# MAGBOT21.net
KiCad netlist of a schematic drawn in EAGLE
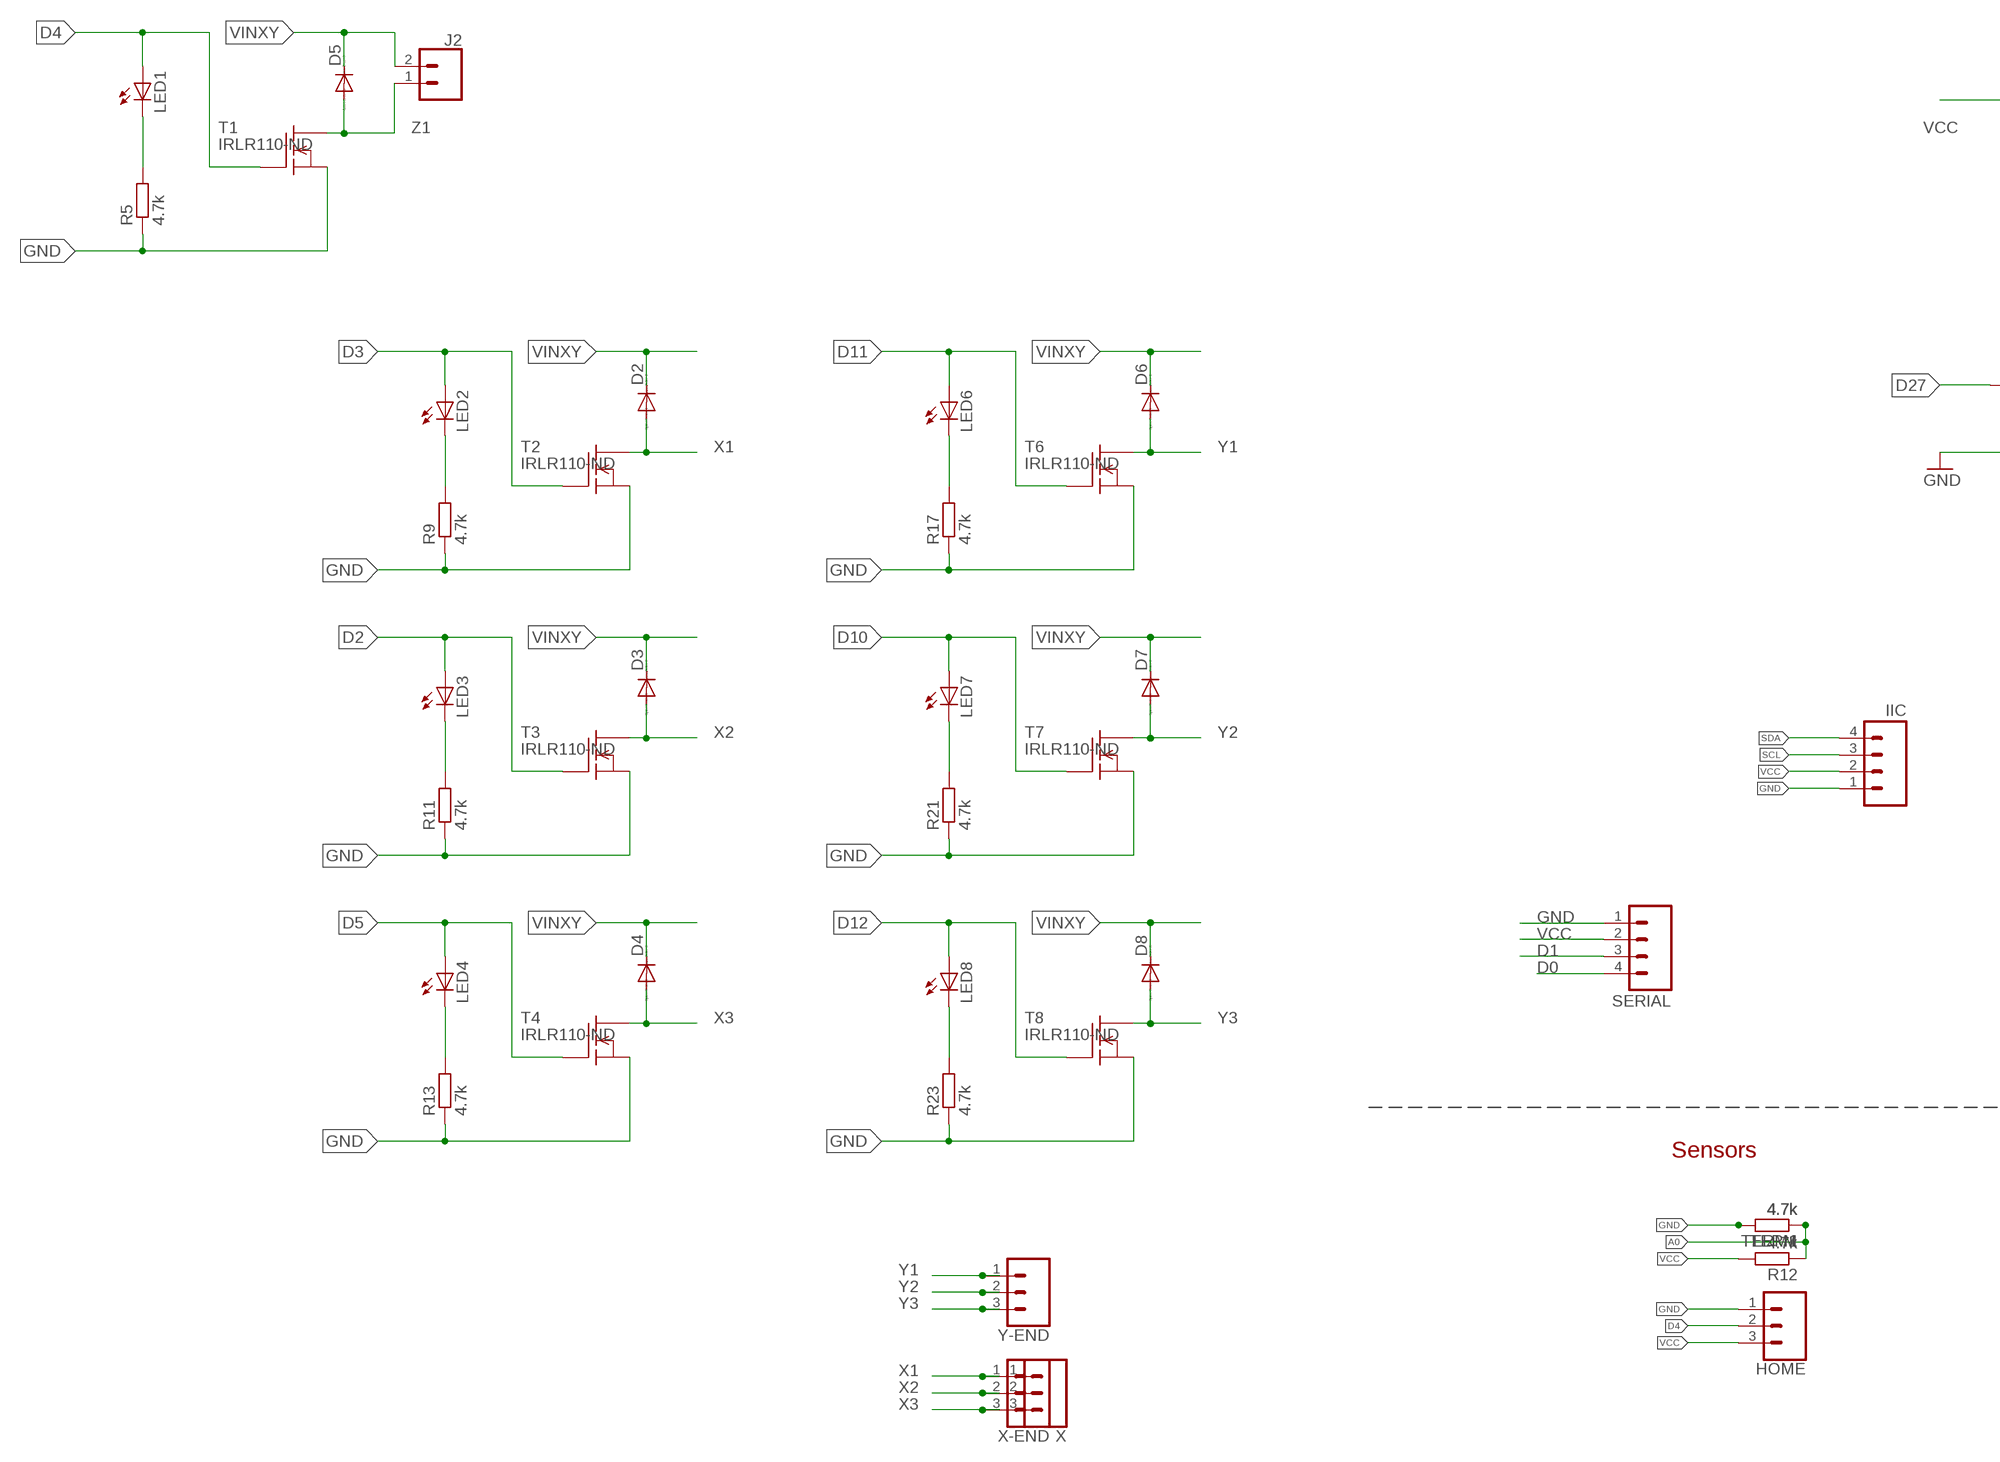
[diagram p0: schematic, sheet 1, part 1 of 2]
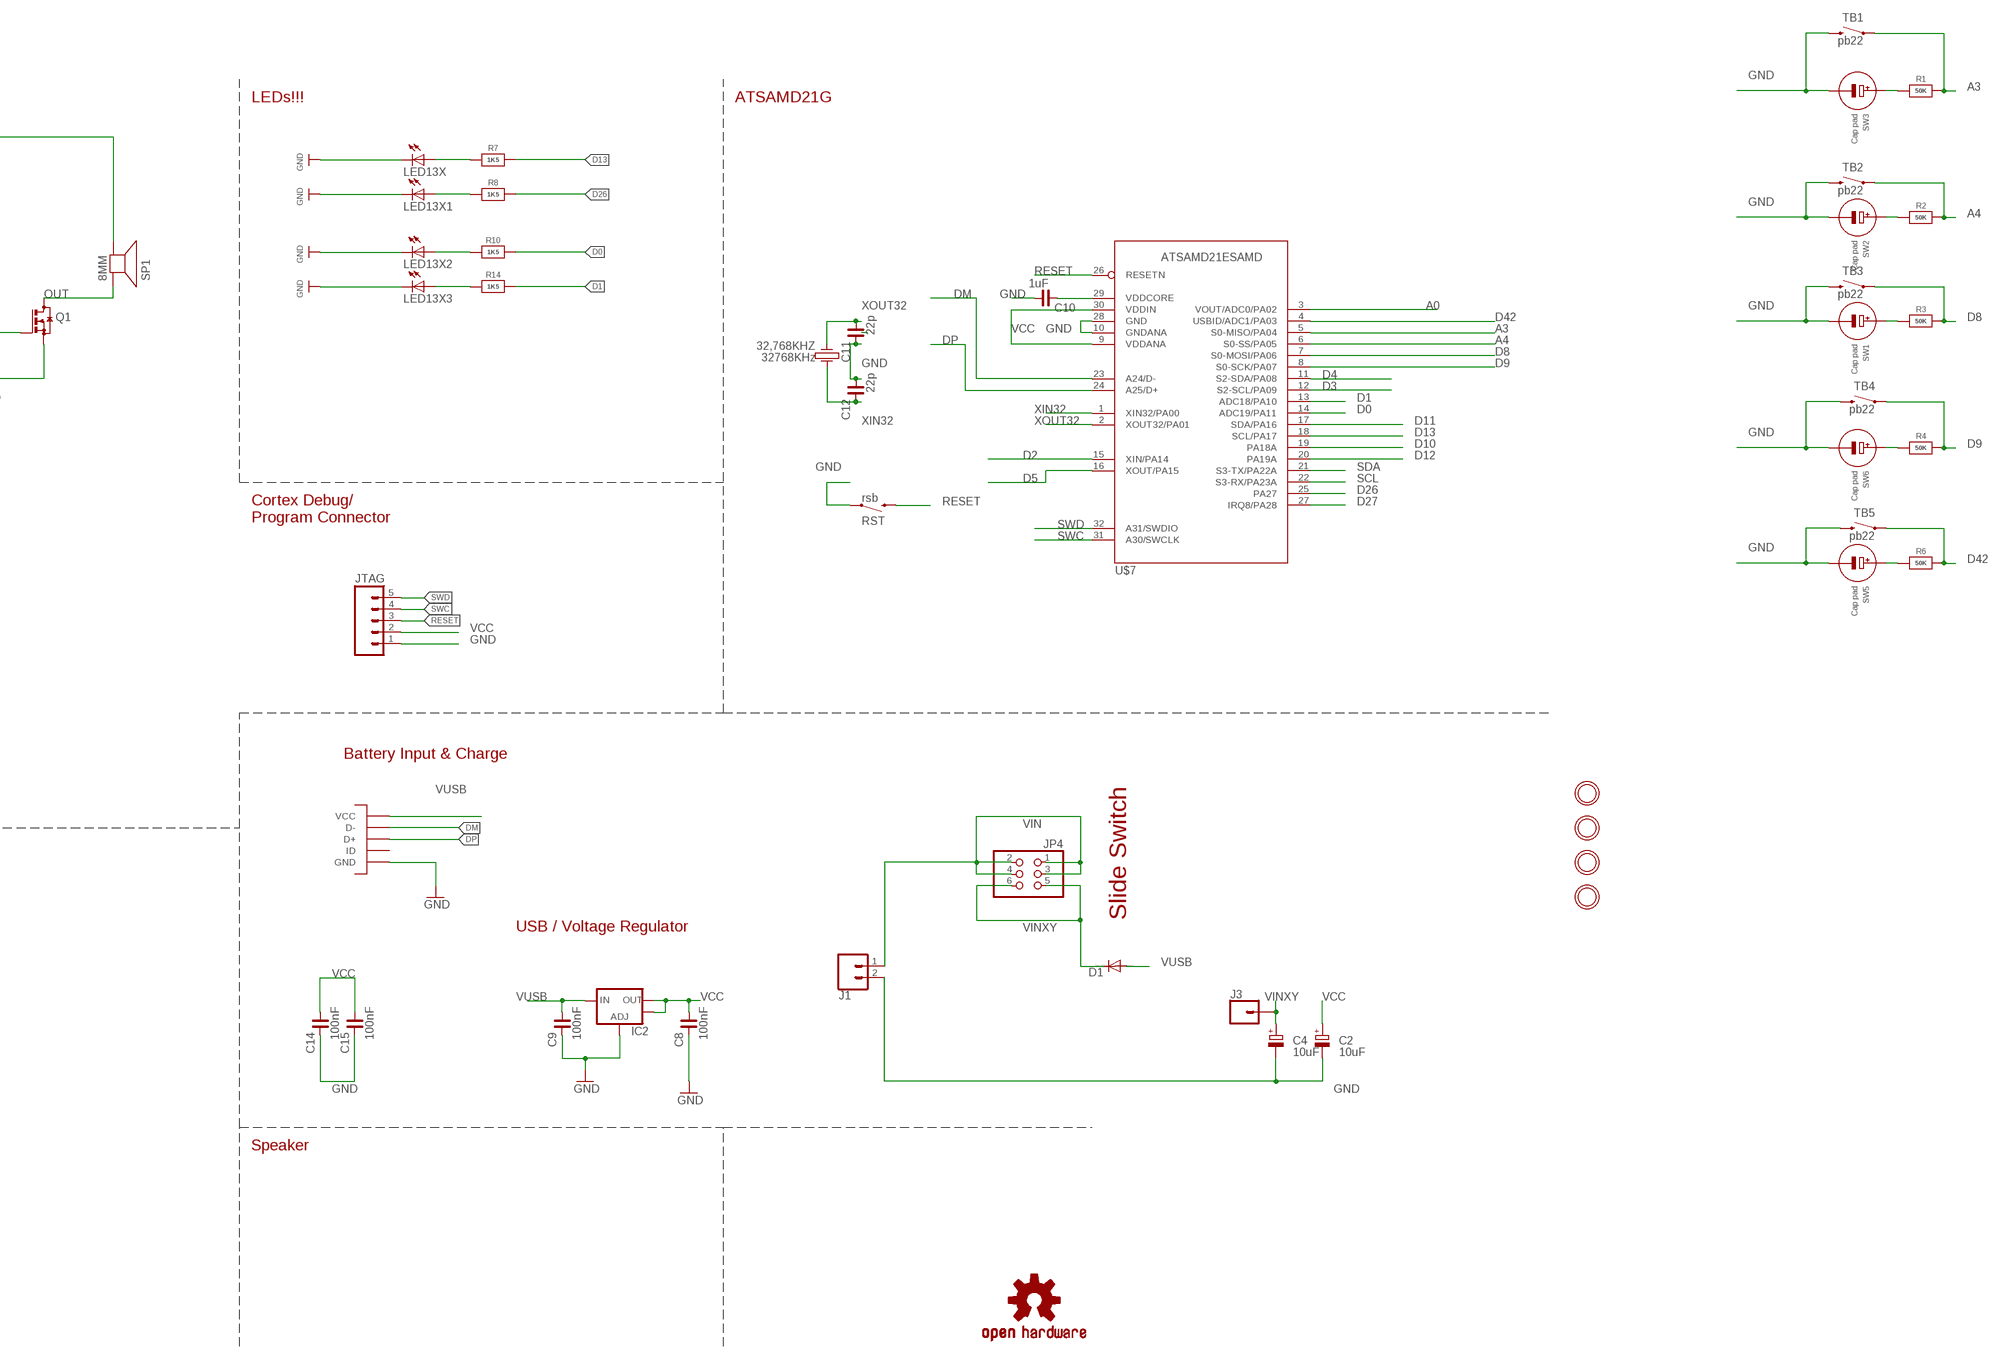
[diagram p1: schematic, sheet 1, part 2 of 2]

(export (version "E")
  (design (tool "Eeschema 10.0.6"))
  (components
    (comp (ref "32,768KHZ")
      (value "32768KHz")
      (footprint "eagle-import:KX-327LT")
      (libsource (lib "eagle-import") (part "CRYSTALL"))
    )
    (comp (ref "C2")
      (value "10uF")
      (footprint "eagle-import:153CLV-0605")
      (libsource (lib "eagle-import") (part "CPOL-EU153CLV-0605"))
    )
    (comp (ref "C4")
      (value "10uF")
      (footprint "eagle-import:153CLV-0605")
      (libsource (lib "eagle-import") (part "CPOL-EU153CLV-0605"))
    )
    (comp (ref "C8")
      (value "100nF")
      (footprint "eagle-import:C0603")
      (libsource (lib "eagle-import") (part "C_0603"))
    )
    (comp (ref "C9")
      (value "100nF")
      (footprint "eagle-import:C0603")
      (libsource (lib "eagle-import") (part "C_0603"))
    )
    (comp (ref "C10")
      (value "1uF")
      (footprint "eagle-import:C0805")
      (libsource (lib "eagle-import") (part "C_0805"))
    )
    (comp (ref "C11")
      (value "22p")
      (footprint "eagle-import:C0805")
      (libsource (lib "eagle-import") (part "C_0805"))
    )
    (comp (ref "C12")
      (value "22p")
      (footprint "eagle-import:C0805")
      (libsource (lib "eagle-import") (part "C_0805"))
    )
    (comp (ref "C14")
      (value "100nF")
      (footprint "eagle-import:C0805")
      (libsource (lib "eagle-import") (part "C_0805"))
    )
    (comp (ref "C15")
      (value "100nF")
      (footprint "eagle-import:C0805")
      (libsource (lib "eagle-import") (part "C_0805"))
    )
    (comp (ref "D1")
      (value "DIODE-DO214AC")
      (footprint "eagle-import:DO214AC")
      (libsource (lib "eagle-import") (part "DIODE-DO214AC"))
    )
    (comp (ref "D2")
      (value "DIODE-DO214AC")
      (footprint "eagle-import:DO214AC")
      (libsource (lib "eagle-import") (part "DIODE-DO214AC"))
    )
    (comp (ref "D3")
      (value "DIODE-DO214AC")
      (footprint "eagle-import:DO214AC")
      (libsource (lib "eagle-import") (part "DIODE-DO214AC"))
    )
    (comp (ref "D4")
      (value "DIODE-DO214AC")
      (footprint "eagle-import:DO214AC")
      (libsource (lib "eagle-import") (part "DIODE-DO214AC"))
    )
    (comp (ref "D5")
      (value "DIODE-DO214AC")
      (footprint "eagle-import:DO214AC")
      (libsource (lib "eagle-import") (part "DIODE-DO214AC"))
    )
    (comp (ref "D6")
      (value "DIODE-DO214AC")
      (footprint "eagle-import:DO214AC")
      (libsource (lib "eagle-import") (part "DIODE-DO214AC"))
    )
    (comp (ref "D7")
      (value "DIODE-DO214AC")
      (footprint "eagle-import:DO214AC")
      (libsource (lib "eagle-import") (part "DIODE-DO214AC"))
    )
    (comp (ref "D8")
      (value "DIODE-DO214AC")
      (footprint "eagle-import:DO214AC")
      (libsource (lib "eagle-import") (part "DIODE-DO214AC"))
    )
    (comp (ref "HOME")
      (value "CONN_031X03_NO_SILK")
      (footprint "eagle-import:1X03_NO_SILK")
      (libsource (lib "eagle-import") (part "CONN_031X03_NO_SILK"))
    )
    (comp (ref "IC2")
      (value "V_REG_LM1117SOT223")
      (footprint "eagle-import:SOT223")
      (libsource (lib "eagle-import") (part "V_REG_LM1117SOT223"))
    )
    (comp (ref "IIC")
      (value "M041X04_NO_SILK")
      (footprint "eagle-import:1X04_NO_SILK")
      (libsource (lib "eagle-import") (part "M041X04_NO_SILK"))
    )
    (comp (ref "J1")
      (value "CONN_02PTH3")
      (footprint "eagle-import:1X02_LONGPADS")
      (libsource (lib "eagle-import") (part "CONN_02PTH3"))
    )
    (comp (ref "J2")
      (value "CONN_02PTH3")
      (footprint "eagle-import:1X02_LONGPADS")
      (libsource (lib "eagle-import") (part "CONN_02PTH3"))
    )
    (comp (ref "J3")
      (value "CONN_01PTH_NO_SILK_KIT")
      (footprint "eagle-import:1X01NS_KIT")
      (libsource (lib "eagle-import") (part "CONN_01PTH_NO_SILK_KIT"))
    )
    (comp (ref "JP4")
      (value "PINHD-2X3")
      (footprint "eagle-import:2X03")
      (libsource (lib "eagle-import") (part "PINHD-2X3"))
    )
    (comp (ref "JTAG")
      (value "M051.27MM")
      (footprint "eagle-import:1X05-1.27MM")
      (libsource (lib "eagle-import") (part "M051.27MM"))
    )
    (comp (ref "LED1")
      (value "LEDCHIPLED_0805")
      (footprint "eagle-import:CHIPLED_0805")
      (libsource (lib "eagle-import") (part "LEDCHIPLED_0805"))
    )
    (comp (ref "LED2")
      (value "LEDCHIPLED_0805")
      (footprint "eagle-import:CHIPLED_0805")
      (libsource (lib "eagle-import") (part "LEDCHIPLED_0805"))
    )
    (comp (ref "LED3")
      (value "LEDCHIPLED_0805")
      (footprint "eagle-import:CHIPLED_0805")
      (libsource (lib "eagle-import") (part "LEDCHIPLED_0805"))
    )
    (comp (ref "LED4")
      (value "LEDCHIPLED_0805")
      (footprint "eagle-import:CHIPLED_0805")
      (libsource (lib "eagle-import") (part "LEDCHIPLED_0805"))
    )
    (comp (ref "LED6")
      (value "LEDCHIPLED_0805")
      (footprint "eagle-import:CHIPLED_0805")
      (libsource (lib "eagle-import") (part "LEDCHIPLED_0805"))
    )
    (comp (ref "LED7")
      (value "LEDCHIPLED_0805")
      (footprint "eagle-import:CHIPLED_0805")
      (libsource (lib "eagle-import") (part "LEDCHIPLED_0805"))
    )
    (comp (ref "LED8")
      (value "LEDCHIPLED_0805")
      (footprint "eagle-import:CHIPLED_0805")
      (libsource (lib "eagle-import") (part "LEDCHIPLED_0805"))
    )
    (comp (ref "LED13X")
      (value "LEDCHIPLED_0805")
      (footprint "eagle-import:CHIPLED_0805")
      (libsource (lib "eagle-import") (part "LEDCHIPLED_0805"))
    )
    (comp (ref "LED13X1")
      (value "LEDCHIPLED_0805")
      (footprint "eagle-import:CHIPLED_0805")
      (libsource (lib "eagle-import") (part "LEDCHIPLED_0805"))
    )
    (comp (ref "LED13X2")
      (value "LEDCHIPLED_0603")
      (footprint "eagle-import:CHIPLED_0603")
      (libsource (lib "eagle-import") (part "LEDCHIPLED_0603"))
    )
    (comp (ref "LED13X3")
      (value "LEDCHIPLED_0603")
      (footprint "eagle-import:CHIPLED_0603")
      (libsource (lib "eagle-import") (part "LEDCHIPLED_0603"))
    )
    (comp (ref "LOGO3")
      (value "OSHW-LOGOS")
      (footprint "eagle-import:OSHW-LOGO-S")
      (libsource (lib "eagle-import") (part "OSHW-LOGOS"))
    )
    (comp (ref "Q1")
      (value "BSS123")
      (footprint "eagle-import:SOT23")
      (libsource (lib "eagle-import") (part "BSS123"))
    )
    (comp (ref "R1")
      (value "50K")
      (footprint "eagle-import:_0805")
      (libsource (lib "eagle-import") (part "RESISTOR_0805"))
    )
    (comp (ref "R2")
      (value "50K")
      (footprint "eagle-import:_0805")
      (libsource (lib "eagle-import") (part "RESISTOR_0805"))
    )
    (comp (ref "R3")
      (value "50K")
      (footprint "eagle-import:_0805")
      (libsource (lib "eagle-import") (part "RESISTOR_0805"))
    )
    (comp (ref "R4")
      (value "50K")
      (footprint "eagle-import:_0805")
      (libsource (lib "eagle-import") (part "RESISTOR_0805"))
    )
    (comp (ref "R5")
      (value "4.7k")
      (footprint "eagle-import:R0603")
      (libsource (lib "eagle-import") (part "R-EU_R0603"))
    )
    (comp (ref "R6")
      (value "50K")
      (footprint "eagle-import:_0805")
      (libsource (lib "eagle-import") (part "RESISTOR_0805"))
    )
    (comp (ref "R7")
      (value "1K5")
      (footprint "eagle-import:_0805MP")
      (libsource (lib "eagle-import") (part "RESISTOR_0805MP"))
    )
    (comp (ref "R8")
      (value "1K5")
      (footprint "eagle-import:0603-NO")
      (libsource (lib "eagle-import") (part "RESISTOR_0603_NOOUT"))
    )
    (comp (ref "R9")
      (value "4.7k")
      (footprint "eagle-import:R0603")
      (libsource (lib "eagle-import") (part "R-EU_R0603"))
    )
    (comp (ref "R10")
      (value "1K5")
      (footprint "eagle-import:_0603MP")
      (libsource (lib "eagle-import") (part "RESISTOR_0603MP"))
    )
    (comp (ref "R11")
      (value "4.7k")
      (footprint "eagle-import:R0603")
      (libsource (lib "eagle-import") (part "R-EU_R0603"))
    )
    (comp (ref "R12")
      (value "4.7k")
      (footprint "eagle-import:R0603")
      (libsource (lib "eagle-import") (part "R-EU_R0603"))
    )
    (comp (ref "R13")
      (value "4.7k")
      (footprint "eagle-import:R0603")
      (libsource (lib "eagle-import") (part "R-EU_R0603"))
    )
    (comp (ref "R14")
      (value "1K5")
      (footprint "eagle-import:_0603MP")
      (libsource (lib "eagle-import") (part "RESISTOR_0603MP"))
    )
    (comp (ref "R17")
      (value "4.7k")
      (footprint "eagle-import:R0603")
      (libsource (lib "eagle-import") (part "R-EU_R0603"))
    )
    (comp (ref "R21")
      (value "4.7k")
      (footprint "eagle-import:R0603")
      (libsource (lib "eagle-import") (part "R-EU_R0603"))
    )
    (comp (ref "R23")
      (value "4.7k")
      (footprint "eagle-import:R0603")
      (libsource (lib "eagle-import") (part "R-EU_R0603"))
    )
    (comp (ref "RST")
      (value "rsb")
      (footprint "eagle-import:TACTILE_SWITCH_SMD-3")
      (libsource (lib "eagle-import") (part "SWITCH-MOMENTARY-2SMD-3"))
    )
    (comp (ref "SERIAL")
      (value "M041X04_NO_SILK")
      (footprint "eagle-import:1X04_NO_SILK")
      (libsource (lib "eagle-import") (part "M041X04_NO_SILK"))
    )
    (comp (ref "SP1")
      (value "8MM")
      (footprint "eagle-import:BUZZER_SMT_5MM")
      (libsource (lib "eagle-import") (part "SPEAKER_BUZZER5MM"))
    )
    (comp (ref "SW1")
      (value "Cap pad")
      (footprint "eagle-import:CAPTOUCH_SIMPLE_12.5MM")
      (libsource (lib "eagle-import") (part "SWITCH_CAPTOUCHATMELAT42QT"))
    )
    (comp (ref "SW2")
      (value "Cap pad")
      (footprint "eagle-import:CAPTOUCH_SIMPLE_12.5MM")
      (libsource (lib "eagle-import") (part "SWITCH_CAPTOUCHATMELAT42QT"))
    )
    (comp (ref "SW3")
      (value "Cap pad")
      (footprint "eagle-import:CAPTOUCH_SIMPLE_12.5MM")
      (libsource (lib "eagle-import") (part "SWITCH_CAPTOUCHATMELAT42QT"))
    )
    (comp (ref "SW5")
      (value "Cap pad")
      (footprint "eagle-import:CAPTOUCH_SIMPLE_12.5MM")
      (libsource (lib "eagle-import") (part "SWITCH_CAPTOUCHATMELAT42QT"))
    )
    (comp (ref "SW6")
      (value "Cap pad")
      (footprint "eagle-import:CAPTOUCH_SIMPLE_12.5MM")
      (libsource (lib "eagle-import") (part "SWITCH_CAPTOUCHATMELAT42QT"))
    )
    (comp (ref "T1")
      (value "IRLR110-ND")
      (footprint "eagle-import:TO252")
      (libsource (lib "eagle-import") (part "IRLR110-ND"))
    )
    (comp (ref "T2")
      (value "IRLR110-ND")
      (footprint "eagle-import:TO252")
      (libsource (lib "eagle-import") (part "IRLR110-ND"))
    )
    (comp (ref "T3")
      (value "IRLR110-ND")
      (footprint "eagle-import:TO252")
      (libsource (lib "eagle-import") (part "IRLR110-ND"))
    )
    (comp (ref "T4")
      (value "IRLR110-ND")
      (footprint "eagle-import:TO252")
      (libsource (lib "eagle-import") (part "IRLR110-ND"))
    )
    (comp (ref "T6")
      (value "IRLR110-ND")
      (footprint "eagle-import:TO252")
      (libsource (lib "eagle-import") (part "IRLR110-ND"))
    )
    (comp (ref "T7")
      (value "IRLR110-ND")
      (footprint "eagle-import:TO252")
      (libsource (lib "eagle-import") (part "IRLR110-ND"))
    )
    (comp (ref "T8")
      (value "IRLR110-ND")
      (footprint "eagle-import:TO252")
      (libsource (lib "eagle-import") (part "IRLR110-ND"))
    )
    (comp (ref "TB1")
      (value "pb22")
      (footprint "eagle-import:TACTILE_SWITCH_SMD-3")
      (libsource (lib "eagle-import") (part "SWITCH-MOMENTARY-2SMD-3"))
    )
    (comp (ref "TB2")
      (value "pb22")
      (footprint "eagle-import:TACTILE_SWITCH_SMD-3")
      (libsource (lib "eagle-import") (part "SWITCH-MOMENTARY-2SMD-3"))
    )
    (comp (ref "TB3")
      (value "pb22")
      (footprint "eagle-import:TACTILE_SWITCH_SMD-3")
      (libsource (lib "eagle-import") (part "SWITCH-MOMENTARY-2SMD-3"))
    )
    (comp (ref "TB4")
      (value "pb22")
      (footprint "eagle-import:TACTILE_SWITCH_SMD-3")
      (libsource (lib "eagle-import") (part "SWITCH-MOMENTARY-2SMD-3"))
    )
    (comp (ref "TB5")
      (value "pb22")
      (footprint "eagle-import:TACTILE_SWITCH_SMD-3")
      (libsource (lib "eagle-import") (part "SWITCH-MOMENTARY-2SMD-3"))
    )
    (comp (ref "TERM")
      (value "4.7k")
      (footprint "eagle-import:R0805W")
      (libsource (lib "eagle-import") (part "R-EU_R0805W"))
    )
    (comp (ref "TERM1")
      (value "4.7k")
      (footprint "eagle-import:R0805W")
      (libsource (lib "eagle-import") (part "R-EU_R0805W"))
    )
    (comp (ref "U$3")
      (value "MOUNTINGHOLE2.0")
      (footprint "eagle-import:MOUNTINGHOLE_2.0_PLATED")
      (libsource (lib "eagle-import") (part "MOUNTINGHOLE2.0"))
    )
    (comp (ref "U$4")
      (value "MOUNTINGHOLE2.0")
      (footprint "eagle-import:MOUNTINGHOLE_2.0_PLATED")
      (libsource (lib "eagle-import") (part "MOUNTINGHOLE2.0"))
    )
    (comp (ref "U$5")
      (value "MICROUSB")
      (footprint "eagle-import:MICRO_B")
      (libsource (lib "eagle-import") (part "MICROUSB"))
    )
    (comp (ref "U$7")
      (value "ATSAMD21ESAMD")
      (footprint "eagle-import:TQFP32-08")
      (libsource (lib "eagle-import") (part "ATSAMD21ESAMD"))
    )
    (comp (ref "U$8")
      (value "MOUNTINGHOLE2.0")
      (footprint "eagle-import:MOUNTINGHOLE_2.0_PLATED")
      (libsource (lib "eagle-import") (part "MOUNTINGHOLE2.0"))
    )
    (comp (ref "U$10")
      (value "MOUNTINGHOLE2.0")
      (footprint "eagle-import:MOUNTINGHOLE_2.0_PLATED")
      (libsource (lib "eagle-import") (part "MOUNTINGHOLE2.0"))
    )
    (comp (ref "X")
      (value "CONN_031X03_NO_SILK")
      (footprint "eagle-import:1X03_NO_SILK")
      (libsource (lib "eagle-import") (part "CONN_031X03_NO_SILK"))
    )
    (comp (ref "X-END")
      (value "CONN_031X03_NO_SILK")
      (footprint "eagle-import:1X03_NO_SILK")
      (libsource (lib "eagle-import") (part "CONN_031X03_NO_SILK"))
    )
    (comp (ref "Y-END")
      (value "CONN_031X03_NO_SILK")
      (footprint "eagle-import:1X03_NO_SILK")
      (libsource (lib "eagle-import") (part "CONN_031X03_NO_SILK"))
    )
  )
  (nets
    (net (code "1") (name "/A3") (class "Default")
      (node (ref "R1") (pin "1") (pinfunction "1_1") (pintype "passive"))
      (node (ref "TB1") (pin "1") (pinfunction "1_1") (pintype "passive"))
      (node (ref "U$7") (pin "5") (pinfunction "S0-MISO/PA04_5") (pintype "bidirectional"))
    )
    (net (code "2") (name "/A4") (class "Default")
      (node (ref "R2") (pin "1") (pinfunction "1_1") (pintype "passive"))
      (node (ref "TB2") (pin "1") (pinfunction "1_1") (pintype "passive"))
      (node (ref "U$7") (pin "6") (pinfunction "S0-SS/PA05_6") (pintype "bidirectional"))
    )
    (net (code "3") (name "/D8") (class "Default")
      (node (ref "R3") (pin "1") (pinfunction "1_1") (pintype "passive"))
      (node (ref "TB3") (pin "1") (pinfunction "1_1") (pintype "passive"))
      (node (ref "U$7") (pin "7") (pinfunction "S0-MOSI/PA06_7") (pintype "bidirectional"))
    )
    (net (code "4") (name "/D9") (class "Default")
      (node (ref "R4") (pin "1") (pinfunction "1_1") (pintype "passive"))
      (node (ref "TB4") (pin "1") (pinfunction "1_1") (pintype "passive"))
      (node (ref "U$7") (pin "8") (pinfunction "S0-SCK/PA07_8") (pintype "bidirectional"))
    )
    (net (code "5") (name "/D42") (class "Default")
      (node (ref "R6") (pin "1") (pinfunction "1_1") (pintype "passive"))
      (node (ref "TB5") (pin "1") (pinfunction "1_1") (pintype "passive"))
      (node (ref "U$7") (pin "4") (pinfunction "USBID/ADC1/PA03_4") (pintype "bidirectional"))
    )
    (net (code "6") (name "/OUT") (class "Default")
      (node (ref "Q1") (pin "3") (pinfunction "D_3") (pintype "passive"))
      (node (ref "SP1") (pin "+") (pinfunction "+_+") (pintype "passive"))
    )
    (net (code "7") (name "/VIN") (class "Default")
      (node (ref "J1") (pin "1") (pinfunction "1_1") (pintype "passive"))
      (node (ref "JP4") (pin "1") (pinfunction "1_1") (pintype "passive"))
      (node (ref "JP4") (pin "2") (pinfunction "2_2") (pintype "passive"))
      (node (ref "JP4") (pin "3") (pinfunction "3_3") (pintype "passive"))
      (node (ref "JP4") (pin "4") (pinfunction "4_4") (pintype "passive"))
    )
    (net (code "8") (name "/VUSB") (class "Default")
      (node (ref "C9") (pin "1") (pinfunction "1_1") (pintype "passive"))
      (node (ref "D1") (pin "A") (pinfunction "A_A") (pintype "passive"))
      (node (ref "IC2") (pin "3") (pinfunction "IN_3") (pintype "input"))
      (node (ref "U$5") (pin "P1") (pinfunction "VCC_P1") (pintype "bidirectional"))
    )
    (net (code "9") (name "/X1") (class "Default")
      (node (ref "D2") (pin "A") (pinfunction "A_A") (pintype "passive"))
      (node (ref "T2") (pin "3") (pinfunction "D_3") (pintype "passive"))
      (node (ref "X") (pin "1") (pinfunction "1_1") (pintype "passive"))
      (node (ref "X-END") (pin "1") (pinfunction "1_1") (pintype "passive"))
    )
    (net (code "10") (name "/X2") (class "Default")
      (node (ref "D3") (pin "A") (pinfunction "A_A") (pintype "passive"))
      (node (ref "T3") (pin "3") (pinfunction "D_3") (pintype "passive"))
      (node (ref "X") (pin "2") (pinfunction "2_2") (pintype "passive"))
      (node (ref "X-END") (pin "2") (pinfunction "2_2") (pintype "passive"))
    )
    (net (code "11") (name "/X3") (class "Default")
      (node (ref "D4") (pin "A") (pinfunction "A_A") (pintype "passive"))
      (node (ref "T4") (pin "3") (pinfunction "D_3") (pintype "passive"))
      (node (ref "X") (pin "3") (pinfunction "3_3") (pintype "passive"))
      (node (ref "X-END") (pin "3") (pinfunction "3_3") (pintype "passive"))
    )
    (net (code "12") (name "/XIN32") (class "Default")
      (node (ref "32,768KHZ") (pin "1") (pinfunction "P$1_1") (pintype "bidirectional"))
      (node (ref "C12") (pin "2") (pinfunction "2_2") (pintype "passive"))
      (node (ref "U$7") (pin "1") (pinfunction "XIN32/PA00_1") (pintype "bidirectional"))
    )
    (net (code "13") (name "/XOUT32") (class "Default")
      (node (ref "32,768KHZ") (pin "4") (pinfunction "P$2_4") (pintype "bidirectional"))
      (node (ref "C11") (pin "1") (pinfunction "1_1") (pintype "passive"))
      (node (ref "U$7") (pin "2") (pinfunction "XOUT32/PA01_2") (pintype "bidirectional"))
    )
    (net (code "14") (name "/Y1") (class "Default")
      (node (ref "D6") (pin "A") (pinfunction "A_A") (pintype "passive"))
      (node (ref "T6") (pin "3") (pinfunction "D_3") (pintype "passive"))
      (node (ref "Y-END") (pin "1") (pinfunction "1_1") (pintype "passive"))
    )
    (net (code "15") (name "/Y2") (class "Default")
      (node (ref "D7") (pin "A") (pinfunction "A_A") (pintype "passive"))
      (node (ref "T7") (pin "3") (pinfunction "D_3") (pintype "passive"))
      (node (ref "Y-END") (pin "2") (pinfunction "2_2") (pintype "passive"))
    )
    (net (code "16") (name "/Y3") (class "Default")
      (node (ref "D8") (pin "A") (pinfunction "A_A") (pintype "passive"))
      (node (ref "T8") (pin "3") (pinfunction "D_3") (pintype "passive"))
      (node (ref "Y-END") (pin "3") (pinfunction "3_3") (pintype "passive"))
    )
    (net (code "17") (name "/Z1") (class "Default")
      (node (ref "D5") (pin "A") (pinfunction "A_A") (pintype "passive"))
      (node (ref "J2") (pin "1") (pinfunction "1_1") (pintype "passive"))
      (node (ref "T1") (pin "3") (pinfunction "D_3") (pintype "passive"))
    )
    (net (code "18") (name "A0") (class "Default")
      (node (ref "R12") (pin "1") (pinfunction "1_1") (pintype "passive"))
      (node (ref "TERM") (pin "1") (pinfunction "1_1") (pintype "passive"))
      (node (ref "TERM1") (pin "1") (pinfunction "1_1") (pintype "passive"))
      (node (ref "U$7") (pin "3") (pinfunction "VOUT/ADC0/PA02_3") (pintype "bidirectional"))
    )
    (net (code "19") (name "D0") (class "Default")
      (node (ref "R10") (pin "1") (pinfunction "1_1") (pintype "passive"))
      (node (ref "SERIAL") (pin "4") (pinfunction "4_4") (pintype "passive"))
      (node (ref "U$7") (pin "14") (pinfunction "ADC19/PA11_14") (pintype "bidirectional"))
    )
    (net (code "20") (name "D1") (class "Default")
      (node (ref "R14") (pin "1") (pinfunction "1_1") (pintype "passive"))
      (node (ref "SERIAL") (pin "3") (pinfunction "3_3") (pintype "passive"))
      (node (ref "U$7") (pin "13") (pinfunction "ADC18/PA10_13") (pintype "bidirectional"))
    )
    (net (code "21") (name "D2") (class "Default")
      (node (ref "LED3") (pin "A") (pinfunction "A_A") (pintype "passive"))
      (node (ref "T3") (pin "1") (pinfunction "G_1") (pintype "passive"))
      (node (ref "U$7") (pin "15") (pinfunction "XIN/PA14_15") (pintype "bidirectional"))
    )
    (net (code "22") (name "D3") (class "Default")
      (node (ref "LED2") (pin "A") (pinfunction "A_A") (pintype "passive"))
      (node (ref "T2") (pin "1") (pinfunction "G_1") (pintype "passive"))
      (node (ref "U$7") (pin "12") (pinfunction "S2-SCL/PA09_12") (pintype "bidirectional"))
    )
    (net (code "23") (name "D4") (class "Default")
      (node (ref "HOME") (pin "2") (pinfunction "2_2") (pintype "passive"))
      (node (ref "LED1") (pin "A") (pinfunction "A_A") (pintype "passive"))
      (node (ref "T1") (pin "1") (pinfunction "G_1") (pintype "passive"))
      (node (ref "U$7") (pin "11") (pinfunction "S2-SDA/PA08_11") (pintype "bidirectional"))
    )
    (net (code "24") (name "D5") (class "Default")
      (node (ref "LED4") (pin "A") (pinfunction "A_A") (pintype "passive"))
      (node (ref "T4") (pin "1") (pinfunction "G_1") (pintype "passive"))
      (node (ref "U$7") (pin "16") (pinfunction "XOUT/PA15_16") (pintype "bidirectional"))
    )
    (net (code "25") (name "D10") (class "Default")
      (node (ref "LED7") (pin "A") (pinfunction "A_A") (pintype "passive"))
      (node (ref "T7") (pin "1") (pinfunction "G_1") (pintype "passive"))
      (node (ref "U$7") (pin "19") (pinfunction "PA18A_19") (pintype "bidirectional"))
    )
    (net (code "26") (name "D11") (class "Default")
      (node (ref "LED6") (pin "A") (pinfunction "A_A") (pintype "passive"))
      (node (ref "T6") (pin "1") (pinfunction "G_1") (pintype "passive"))
      (node (ref "U$7") (pin "17") (pinfunction "SDA/PA16_17") (pintype "bidirectional"))
    )
    (net (code "27") (name "D12") (class "Default")
      (node (ref "LED8") (pin "A") (pinfunction "A_A") (pintype "passive"))
      (node (ref "T8") (pin "1") (pinfunction "G_1") (pintype "passive"))
      (node (ref "U$7") (pin "20") (pinfunction "PA19A_20") (pintype "bidirectional"))
    )
    (net (code "28") (name "D13") (class "Default")
      (node (ref "R7") (pin "1") (pinfunction "1_1") (pintype "passive"))
      (node (ref "U$7") (pin "18") (pinfunction "SCL/PA17_18") (pintype "bidirectional"))
    )
    (net (code "29") (name "D26") (class "Default")
      (node (ref "R8") (pin "1") (pinfunction "1_1") (pintype "passive"))
      (node (ref "U$7") (pin "25") (pinfunction "PA27_25") (pintype "bidirectional"))
    )
    (net (code "30") (name "D27") (class "Default")
      (node (ref "Q1") (pin "1") (pinfunction "G_1") (pintype "passive"))
      (node (ref "U$7") (pin "27") (pinfunction "IRQ8/PA28_27") (pintype "bidirectional"))
    )
    (net (code "31") (name "DM") (class "Default")
      (node (ref "U$5") (pin "P2") (pinfunction "D-_P2") (pintype "bidirectional"))
      (node (ref "U$7") (pin "23") (pinfunction "A24/D-_23") (pintype "bidirectional"))
    )
    (net (code "32") (name "DP") (class "Default")
      (node (ref "U$5") (pin "P3") (pinfunction "D+_P3") (pintype "bidirectional"))
      (node (ref "U$7") (pin "24") (pinfunction "A25/D+_24") (pintype "bidirectional"))
    )
    (net (code "33") (name "GND") (class "Default")
      (node (ref "C10") (pin "1") (pinfunction "1_1") (pintype "passive"))
      (node (ref "C11") (pin "2") (pinfunction "2_2") (pintype "passive"))
      (node (ref "C12") (pin "1") (pinfunction "1_1") (pintype "passive"))
      (node (ref "C14") (pin "2") (pinfunction "2_2") (pintype "passive"))
      (node (ref "C15") (pin "2") (pinfunction "2_2") (pintype "passive"))
      (node (ref "C2") (pin "-") (pinfunction "-_-") (pintype "passive"))
      (node (ref "C4") (pin "-") (pinfunction "-_-") (pintype "passive"))
      (node (ref "C8") (pin "2") (pinfunction "2_2") (pintype "passive"))
      (node (ref "C9") (pin "2") (pinfunction "2_2") (pintype "passive"))
      (node (ref "HOME") (pin "1") (pinfunction "1_1") (pintype "passive"))
      (node (ref "IC2") (pin "1") (pinfunction "ADJ_1") (pintype "input"))
      (node (ref "IIC") (pin "1") (pinfunction "1_1") (pintype "passive"))
      (node (ref "J1") (pin "2") (pinfunction "2_2") (pintype "passive"))
      (node (ref "JTAG") (pin "1") (pinfunction "1_1") (pintype "passive"))
      (node (ref "LED13X") (pin "C") (pinfunction "C_C") (pintype "passive"))
      (node (ref "LED13X1") (pin "C") (pinfunction "C_C") (pintype "passive"))
      (node (ref "LED13X2") (pin "C") (pinfunction "C_C") (pintype "passive"))
      (node (ref "LED13X3") (pin "C") (pinfunction "C_C") (pintype "passive"))
      (node (ref "Q1") (pin "2") (pinfunction "S_2") (pintype "passive"))
      (node (ref "R11") (pin "1") (pinfunction "1_1") (pintype "passive"))
      (node (ref "R13") (pin "1") (pinfunction "1_1") (pintype "passive"))
      (node (ref "R17") (pin "1") (pinfunction "1_1") (pintype "passive"))
      (node (ref "R21") (pin "1") (pinfunction "1_1") (pintype "passive"))
      (node (ref "R23") (pin "1") (pinfunction "1_1") (pintype "passive"))
      (node (ref "R5") (pin "1") (pinfunction "1_1") (pintype "passive"))
      (node (ref "R9") (pin "1") (pinfunction "1_1") (pintype "passive"))
      (node (ref "RST") (pin "1") (pinfunction "1_1") (pintype "passive"))
      (node (ref "SERIAL") (pin "1") (pinfunction "1_1") (pintype "passive"))
      (node (ref "SW1") (pin "G") (pinfunction "-_G") (pintype "passive"))
      (node (ref "SW2") (pin "G") (pinfunction "-_G") (pintype "passive"))
      (node (ref "SW3") (pin "G") (pinfunction "-_G") (pintype "passive"))
      (node (ref "SW5") (pin "G") (pinfunction "-_G") (pintype "passive"))
      (node (ref "SW6") (pin "G") (pinfunction "-_G") (pintype "passive"))
      (node (ref "T1") (pin "2") (pinfunction "S_2") (pintype "passive"))
      (node (ref "T2") (pin "2") (pinfunction "S_2") (pintype "passive"))
      (node (ref "T3") (pin "2") (pinfunction "S_2") (pintype "passive"))
      (node (ref "T4") (pin "2") (pinfunction "S_2") (pintype "passive"))
      (node (ref "T6") (pin "2") (pinfunction "S_2") (pintype "passive"))
      (node (ref "T7") (pin "2") (pinfunction "S_2") (pintype "passive"))
      (node (ref "T8") (pin "2") (pinfunction "S_2") (pintype "passive"))
      (node (ref "TB1") (pin "4") (pinfunction "2_4") (pintype "passive"))
      (node (ref "TB2") (pin "4") (pinfunction "2_4") (pintype "passive"))
      (node (ref "TB3") (pin "4") (pinfunction "2_4") (pintype "passive"))
      (node (ref "TB4") (pin "4") (pinfunction "2_4") (pintype "passive"))
      (node (ref "TB5") (pin "4") (pinfunction "2_4") (pintype "passive"))
      (node (ref "TERM") (pin "2") (pinfunction "2_2") (pintype "passive"))
      (node (ref "TERM1") (pin "2") (pinfunction "2_2") (pintype "passive"))
      (node (ref "U$5") (pin "GND1") (pinfunction "GND_GND1") (pintype "bidirectional"))
      (node (ref "U$5") (pin "GND2") (pinfunction "GND_GND2") (pintype "bidirectional"))
      (node (ref "U$5") (pin "GND3") (pinfunction "GND_GND3") (pintype "bidirectional"))
      (node (ref "U$5") (pin "GND4") (pinfunction "GND_GND4") (pintype "bidirectional"))
      (node (ref "U$5") (pin "GND7") (pinfunction "GND_GND7") (pintype "bidirectional"))
      (node (ref "U$5") (pin "GND8") (pinfunction "GND_GND8") (pintype "bidirectional"))
      (node (ref "U$5") (pin "P5") (pinfunction "GND_P5") (pintype "bidirectional"))
      (node (ref "U$7") (pin "10") (pinfunction "GNDANA_10") (pintype "bidirectional"))
      (node (ref "U$7") (pin "28") (pinfunction "GND_28") (pintype "bidirectional"))
    )
    (net (code "34") (name "Net-(LED1-PadC)") (class "Default")
      (node (ref "LED1") (pin "C") (pinfunction "C_C") (pintype "passive"))
      (node (ref "R5") (pin "2") (pinfunction "2_2") (pintype "passive"))
    )
    (net (code "35") (name "Net-(LED2-PadC)") (class "Default")
      (node (ref "LED2") (pin "C") (pinfunction "C_C") (pintype "passive"))
      (node (ref "R9") (pin "2") (pinfunction "2_2") (pintype "passive"))
    )
    (net (code "36") (name "Net-(LED3-PadC)") (class "Default")
      (node (ref "LED3") (pin "C") (pinfunction "C_C") (pintype "passive"))
      (node (ref "R11") (pin "2") (pinfunction "2_2") (pintype "passive"))
    )
    (net (code "37") (name "Net-(LED4-PadC)") (class "Default")
      (node (ref "LED4") (pin "C") (pinfunction "C_C") (pintype "passive"))
      (node (ref "R13") (pin "2") (pinfunction "2_2") (pintype "passive"))
    )
    (net (code "38") (name "Net-(LED6-PadC)") (class "Default")
      (node (ref "LED6") (pin "C") (pinfunction "C_C") (pintype "passive"))
      (node (ref "R17") (pin "2") (pinfunction "2_2") (pintype "passive"))
    )
    (net (code "39") (name "Net-(LED7-PadC)") (class "Default")
      (node (ref "LED7") (pin "C") (pinfunction "C_C") (pintype "passive"))
      (node (ref "R21") (pin "2") (pinfunction "2_2") (pintype "passive"))
    )
    (net (code "40") (name "Net-(LED8-PadC)") (class "Default")
      (node (ref "LED8") (pin "C") (pinfunction "C_C") (pintype "passive"))
      (node (ref "R23") (pin "2") (pinfunction "2_2") (pintype "passive"))
    )
    (net (code "41") (name "Net-(LED13X-PadA)") (class "Default")
      (node (ref "LED13X") (pin "A") (pinfunction "A_A") (pintype "passive"))
      (node (ref "R7") (pin "2") (pinfunction "2_2") (pintype "passive"))
    )
    (net (code "42") (name "Net-(LED13X1-PadA)") (class "Default")
      (node (ref "LED13X1") (pin "A") (pinfunction "A_A") (pintype "passive"))
      (node (ref "R8") (pin "2") (pinfunction "2_2") (pintype "passive"))
    )
    (net (code "43") (name "Net-(LED13X2-PadA)") (class "Default")
      (node (ref "LED13X2") (pin "A") (pinfunction "A_A") (pintype "passive"))
      (node (ref "R10") (pin "2") (pinfunction "2_2") (pintype "passive"))
    )
    (net (code "44") (name "Net-(LED13X3-PadA)") (class "Default")
      (node (ref "LED13X3") (pin "A") (pinfunction "A_A") (pintype "passive"))
      (node (ref "R14") (pin "2") (pinfunction "2_2") (pintype "passive"))
    )
    (net (code "45") (name "Net-(SW1-+)") (class "Default")
      (node (ref "R3") (pin "2") (pinfunction "2_2") (pintype "passive"))
      (node (ref "SW1") (pin "E") (pinfunction "+_E") (pintype "passive"))
    )
    (net (code "46") (name "Net-(SW2-+)") (class "Default")
      (node (ref "R2") (pin "2") (pinfunction "2_2") (pintype "passive"))
      (node (ref "SW2") (pin "E") (pinfunction "+_E") (pintype "passive"))
    )
    (net (code "47") (name "Net-(SW3-+)") (class "Default")
      (node (ref "R1") (pin "2") (pinfunction "2_2") (pintype "passive"))
      (node (ref "SW3") (pin "E") (pinfunction "+_E") (pintype "passive"))
    )
    (net (code "48") (name "Net-(SW5-+)") (class "Default")
      (node (ref "R6") (pin "2") (pinfunction "2_2") (pintype "passive"))
      (node (ref "SW5") (pin "E") (pinfunction "+_E") (pintype "passive"))
    )
    (net (code "49") (name "Net-(SW6-+)") (class "Default")
      (node (ref "R4") (pin "2") (pinfunction "2_2") (pintype "passive"))
      (node (ref "SW6") (pin "E") (pinfunction "+_E") (pintype "passive"))
    )
    (net (code "50") (name "Net-(U$7-VDDCORE)") (class "Default")
      (node (ref "C10") (pin "2") (pinfunction "2_2") (pintype "passive"))
      (node (ref "U$7") (pin "29") (pinfunction "VDDCORE_29") (pintype "bidirectional"))
    )
    (net (code "51") (name "RESET") (class "Default")
      (node (ref "JTAG") (pin "3") (pinfunction "3_3") (pintype "passive"))
      (node (ref "RST") (pin "4") (pinfunction "2_4") (pintype "passive"))
      (node (ref "U$7") (pin "26") (pinfunction "RESETN_26") (pintype "bidirectional"))
    )
    (net (code "52") (name "SCL") (class "Default")
      (node (ref "IIC") (pin "3") (pinfunction "3_3") (pintype "passive"))
      (node (ref "U$7") (pin "22") (pinfunction "S3-RX/PA23A_22") (pintype "bidirectional"))
    )
    (net (code "53") (name "SDA") (class "Default")
      (node (ref "IIC") (pin "4") (pinfunction "4_4") (pintype "passive"))
      (node (ref "U$7") (pin "21") (pinfunction "S3-TX/PA22A_21") (pintype "bidirectional"))
    )
    (net (code "54") (name "SWC") (class "Default")
      (node (ref "JTAG") (pin "4") (pinfunction "4_4") (pintype "passive"))
      (node (ref "U$7") (pin "31") (pinfunction "A30/SWCLK_31") (pintype "bidirectional"))
    )
    (net (code "55") (name "SWD") (class "Default")
      (node (ref "JTAG") (pin "5") (pinfunction "5_5") (pintype "passive"))
      (node (ref "U$7") (pin "32") (pinfunction "A31/SWDIO_32") (pintype "bidirectional"))
    )
    (net (code "56") (name "VCC") (class "Default")
      (node (ref "C14") (pin "1") (pinfunction "1_1") (pintype "passive"))
      (node (ref "C15") (pin "1") (pinfunction "1_1") (pintype "passive"))
      (node (ref "C2") (pin "+") (pinfunction "+_+") (pintype "passive"))
      (node (ref "C8") (pin "1") (pinfunction "1_1") (pintype "passive"))
      (node (ref "HOME") (pin "3") (pinfunction "3_3") (pintype "passive"))
      (node (ref "IC2") (pin "2") (pinfunction "OUT_2") (pintype "output"))
      (node (ref "IC2") (pin "4") (pinfunction "OUT_4") (pintype "output"))
      (node (ref "IIC") (pin "2") (pinfunction "2_2") (pintype "passive"))
      (node (ref "JTAG") (pin "2") (pinfunction "2_2") (pintype "passive"))
      (node (ref "R12") (pin "2") (pinfunction "2_2") (pintype "passive"))
      (node (ref "SERIAL") (pin "2") (pinfunction "2_2") (pintype "passive"))
      (node (ref "SP1") (pin "-") (pinfunction "-_-") (pintype "passive"))
      (node (ref "U$7") (pin "30") (pinfunction "VDDIN_30") (pintype "bidirectional"))
      (node (ref "U$7") (pin "9") (pinfunction "VDDANA_9") (pintype "bidirectional"))
    )
    (net (code "57") (name "VINXY") (class "Default")
      (node (ref "C4") (pin "+") (pinfunction "+_+") (pintype "passive"))
      (node (ref "D1") (pin "C") (pinfunction "C_C") (pintype "passive"))
      (node (ref "D2") (pin "C") (pinfunction "C_C") (pintype "passive"))
      (node (ref "D3") (pin "C") (pinfunction "C_C") (pintype "passive"))
      (node (ref "D4") (pin "C") (pinfunction "C_C") (pintype "passive"))
      (node (ref "D5") (pin "C") (pinfunction "C_C") (pintype "passive"))
      (node (ref "D6") (pin "C") (pinfunction "C_C") (pintype "passive"))
      (node (ref "D7") (pin "C") (pinfunction "C_C") (pintype "passive"))
      (node (ref "D8") (pin "C") (pinfunction "C_C") (pintype "passive"))
      (node (ref "J2") (pin "2") (pinfunction "2_2") (pintype "passive"))
      (node (ref "J3") (pin "1") (pinfunction "1_1") (pintype "passive"))
      (node (ref "JP4") (pin "5") (pinfunction "5_5") (pintype "passive"))
      (node (ref "JP4") (pin "6") (pinfunction "6_6") (pintype "passive"))
    )
    (net (code "58") (name "unconnected-(U$5-ID-PadP4)") (class "Default")
      (node (ref "U$5") (pin "P4") (pinfunction "ID_P4") (pintype "bidirectional"))
    )
  )
)
